# stm32_bob.net
KiCad netlist of a schematic drawn in EAGLE
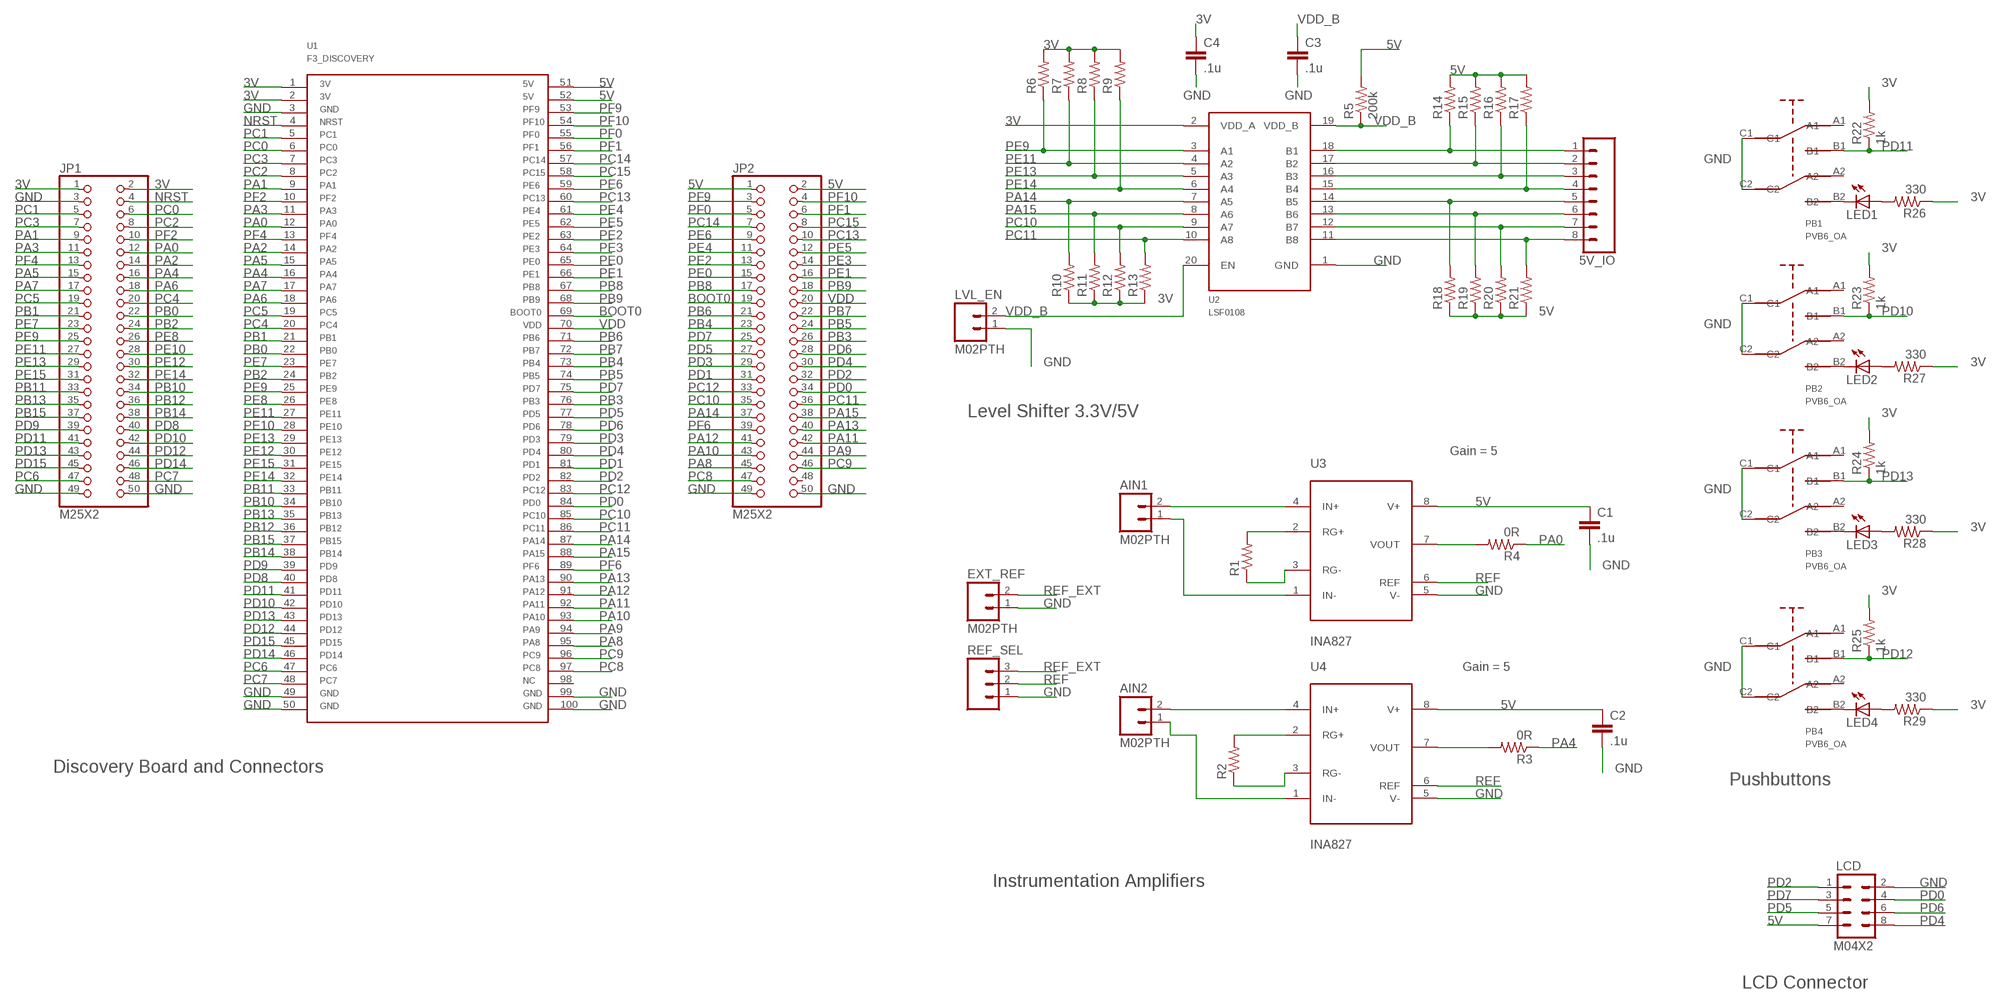
[diagram p0: schematic, sheet 1]

(export (version "E")
  (design (tool "Eeschema 10.0.6"))
  (components
    (comp (ref "5V_IO")
      (value "M081X08")
      (footprint "eagle-import:1X08")
      (libsource (lib "eagle-import") (part "M081X08"))
    )
    (comp (ref "AIN1")
      (value "M02PTH")
      (footprint "eagle-import:1X02")
      (libsource (lib "eagle-import") (part "M02PTH"))
    )
    (comp (ref "AIN2")
      (value "M02PTH")
      (footprint "eagle-import:1X02")
      (libsource (lib "eagle-import") (part "M02PTH"))
    )
    (comp (ref "C1")
      (value ".1u")
      (footprint "eagle-import:C0805")
      (libsource (lib "eagle-import") (part "C-EUC0805"))
    )
    (comp (ref "C2")
      (value ".1u")
      (footprint "eagle-import:C0805")
      (libsource (lib "eagle-import") (part "C-EUC0805"))
    )
    (comp (ref "C3")
      (value ".1u")
      (footprint "eagle-import:C0805")
      (libsource (lib "eagle-import") (part "C-EUC0805"))
    )
    (comp (ref "C4")
      (value ".1u")
      (footprint "eagle-import:C0805")
      (libsource (lib "eagle-import") (part "C-EUC0805"))
    )
    (comp (ref "EXT_REF")
      (value "M02PTH")
      (footprint "eagle-import:1X02")
      (libsource (lib "eagle-import") (part "M02PTH"))
    )
    (comp (ref "JP1")
      (value "M25X2")
      (footprint "eagle-import:2X25")
      (libsource (lib "eagle-import") (part "M25X2"))
    )
    (comp (ref "JP2")
      (value "M25X2")
      (footprint "eagle-import:2X25")
      (libsource (lib "eagle-import") (part "M25X2"))
    )
    (comp (ref "LCD")
      (value "M04X2")
      (footprint "eagle-import:2X4")
      (libsource (lib "eagle-import") (part "M04X2"))
    )
    (comp (ref "LED1")
      (value "LED1206")
      (footprint "eagle-import:LED-1206")
      (libsource (lib "eagle-import") (part "LED1206"))
    )
    (comp (ref "LED2")
      (value "LED1206")
      (footprint "eagle-import:LED-1206")
      (libsource (lib "eagle-import") (part "LED1206"))
    )
    (comp (ref "LED3")
      (value "LED1206")
      (footprint "eagle-import:LED-1206")
      (libsource (lib "eagle-import") (part "LED1206"))
    )
    (comp (ref "LED4")
      (value "LED1206")
      (footprint "eagle-import:LED-1206")
      (libsource (lib "eagle-import") (part "LED1206"))
    )
    (comp (ref "LVL_EN")
      (value "M02PTH")
      (footprint "eagle-import:1X02")
      (libsource (lib "eagle-import") (part "M02PTH"))
    )
    (comp (ref "PB1")
      (value "PVB6_OA")
      (footprint "eagle-import:PVB6_OA")
      (libsource (lib "eagle-import") (part "PVB6_OA"))
    )
    (comp (ref "PB2")
      (value "PVB6_OA")
      (footprint "eagle-import:PVB6_OA")
      (libsource (lib "eagle-import") (part "PVB6_OA"))
    )
    (comp (ref "PB3")
      (value "PVB6_OA")
      (footprint "eagle-import:PVB6_OA")
      (libsource (lib "eagle-import") (part "PVB6_OA"))
    )
    (comp (ref "PB4")
      (value "PVB6_OA")
      (footprint "eagle-import:PVB6_OA")
      (libsource (lib "eagle-import") (part "PVB6_OA"))
    )
    (comp (ref "R1")
      (value "R-US_R1206")
      (footprint "eagle-import:R1206")
      (libsource (lib "eagle-import") (part "R-US_R1206"))
    )
    (comp (ref "R2")
      (value "R-US_R1206")
      (footprint "eagle-import:R1206")
      (libsource (lib "eagle-import") (part "R-US_R1206"))
    )
    (comp (ref "R3")
      (value "0R")
      (footprint "eagle-import:R1206")
      (libsource (lib "eagle-import") (part "R-US_R1206"))
    )
    (comp (ref "R4")
      (value "0R")
      (footprint "eagle-import:R1206")
      (libsource (lib "eagle-import") (part "R-US_R1206"))
    )
    (comp (ref "R5")
      (value "200k")
      (footprint "eagle-import:R0805")
      (libsource (lib "eagle-import") (part "R-US_R0805"))
    )
    (comp (ref "R6")
      (value "R-US_R0805")
      (footprint "eagle-import:R0805")
      (libsource (lib "eagle-import") (part "R-US_R0805"))
    )
    (comp (ref "R7")
      (value "R-US_R0805")
      (footprint "eagle-import:R0805")
      (libsource (lib "eagle-import") (part "R-US_R0805"))
    )
    (comp (ref "R8")
      (value "R-US_R0805")
      (footprint "eagle-import:R0805")
      (libsource (lib "eagle-import") (part "R-US_R0805"))
    )
    (comp (ref "R9")
      (value "R-US_R0805")
      (footprint "eagle-import:R0805")
      (libsource (lib "eagle-import") (part "R-US_R0805"))
    )
    (comp (ref "R10")
      (value "R-US_R0805")
      (footprint "eagle-import:R0805")
      (libsource (lib "eagle-import") (part "R-US_R0805"))
    )
    (comp (ref "R11")
      (value "R-US_R0805")
      (footprint "eagle-import:R0805")
      (libsource (lib "eagle-import") (part "R-US_R0805"))
    )
    (comp (ref "R12")
      (value "R-US_R0805")
      (footprint "eagle-import:R0805")
      (libsource (lib "eagle-import") (part "R-US_R0805"))
    )
    (comp (ref "R13")
      (value "R-US_R0805")
      (footprint "eagle-import:R0805")
      (libsource (lib "eagle-import") (part "R-US_R0805"))
    )
    (comp (ref "R14")
      (value "R-US_R0805")
      (footprint "eagle-import:R0805")
      (libsource (lib "eagle-import") (part "R-US_R0805"))
    )
    (comp (ref "R15")
      (value "R-US_R0805")
      (footprint "eagle-import:R0805")
      (libsource (lib "eagle-import") (part "R-US_R0805"))
    )
    (comp (ref "R16")
      (value "R-US_R0805")
      (footprint "eagle-import:R0805")
      (libsource (lib "eagle-import") (part "R-US_R0805"))
    )
    (comp (ref "R17")
      (value "R-US_R0805")
      (footprint "eagle-import:R0805")
      (libsource (lib "eagle-import") (part "R-US_R0805"))
    )
    (comp (ref "R18")
      (value "R-US_R0805")
      (footprint "eagle-import:R0805")
      (libsource (lib "eagle-import") (part "R-US_R0805"))
    )
    (comp (ref "R19")
      (value "R-US_R0805")
      (footprint "eagle-import:R0805")
      (libsource (lib "eagle-import") (part "R-US_R0805"))
    )
    (comp (ref "R20")
      (value "R-US_R0805")
      (footprint "eagle-import:R0805")
      (libsource (lib "eagle-import") (part "R-US_R0805"))
    )
    (comp (ref "R21")
      (value "R-US_R0805")
      (footprint "eagle-import:R0805")
      (libsource (lib "eagle-import") (part "R-US_R0805"))
    )
    (comp (ref "R22")
      (value "1k")
      (footprint "eagle-import:R0805")
      (libsource (lib "eagle-import") (part "R-US_R0805"))
    )
    (comp (ref "R23")
      (value "1k")
      (footprint "eagle-import:R0805")
      (libsource (lib "eagle-import") (part "R-US_R0805"))
    )
    (comp (ref "R24")
      (value "1k")
      (footprint "eagle-import:R0805")
      (libsource (lib "eagle-import") (part "R-US_R0805"))
    )
    (comp (ref "R25")
      (value "1k")
      (footprint "eagle-import:R0805")
      (libsource (lib "eagle-import") (part "R-US_R0805"))
    )
    (comp (ref "R26")
      (value "330")
      (footprint "eagle-import:R0805")
      (libsource (lib "eagle-import") (part "R-US_R0805"))
    )
    (comp (ref "R27")
      (value "330")
      (footprint "eagle-import:R0805")
      (libsource (lib "eagle-import") (part "R-US_R0805"))
    )
    (comp (ref "R28")
      (value "330")
      (footprint "eagle-import:R0805")
      (libsource (lib "eagle-import") (part "R-US_R0805"))
    )
    (comp (ref "R29")
      (value "330")
      (footprint "eagle-import:R0805")
      (libsource (lib "eagle-import") (part "R-US_R0805"))
    )
    (comp (ref "REF_SEL")
      (value "M03PTH")
      (footprint "eagle-import:1X03")
      (libsource (lib "eagle-import") (part "M03PTH"))
    )
    (comp (ref "U1")
      (value "F3_DISCOVERY")
      (footprint "eagle-import:F3_DISCOVERY")
      (libsource (lib "eagle-import") (part "F3_DISCOVERY"))
    )
    (comp (ref "U2")
      (value "LSF0108")
      (footprint "eagle-import:LSF0108")
      (libsource (lib "eagle-import") (part "LSF0108"))
    )
    (comp (ref "U3")
      (value "INA827")
      (footprint "eagle-import:MSOP8")
      (libsource (lib "eagle-import") (part "INA827"))
    )
    (comp (ref "U4")
      (value "INA827")
      (footprint "eagle-import:MSOP8")
      (libsource (lib "eagle-import") (part "INA827"))
    )
  )
  (nets
    (net (code "1") (name "/3V") (class "Default")
      (node (ref "C4") (pin "1") (pinfunction "1_1") (pintype "passive"))
      (node (ref "JP1") (pin "1") (pinfunction "1_1") (pintype "passive"))
      (node (ref "JP1") (pin "2") (pinfunction "2_2") (pintype "passive"))
      (node (ref "R10") (pin "1") (pinfunction "1_1") (pintype "passive"))
      (node (ref "R11") (pin "1") (pinfunction "1_1") (pintype "passive"))
      (node (ref "R12") (pin "1") (pinfunction "1_1") (pintype "passive"))
      (node (ref "R13") (pin "1") (pinfunction "1_1") (pintype "passive"))
      (node (ref "R22") (pin "2") (pinfunction "2_2") (pintype "passive"))
      (node (ref "R23") (pin "2") (pinfunction "2_2") (pintype "passive"))
      (node (ref "R24") (pin "2") (pinfunction "2_2") (pintype "passive"))
      (node (ref "R25") (pin "2") (pinfunction "2_2") (pintype "passive"))
      (node (ref "R26") (pin "1") (pinfunction "1_1") (pintype "passive"))
      (node (ref "R27") (pin "1") (pinfunction "1_1") (pintype "passive"))
      (node (ref "R28") (pin "1") (pinfunction "1_1") (pintype "passive"))
      (node (ref "R29") (pin "1") (pinfunction "1_1") (pintype "passive"))
      (node (ref "R6") (pin "2") (pinfunction "2_2") (pintype "passive"))
      (node (ref "R7") (pin "2") (pinfunction "2_2") (pintype "passive"))
      (node (ref "R8") (pin "2") (pinfunction "2_2") (pintype "passive"))
      (node (ref "R9") (pin "2") (pinfunction "2_2") (pintype "passive"))
      (node (ref "U1") (pin "1") (pinfunction "P$1_1") (pintype "bidirectional"))
      (node (ref "U1") (pin "2") (pinfunction "P$2_2") (pintype "bidirectional"))
      (node (ref "U2") (pin "2") (pinfunction "VDD_A_2") (pintype "bidirectional"))
    )
    (net (code "2") (name "/5V") (class "Default")
      (node (ref "C1") (pin "1") (pinfunction "1_1") (pintype "passive"))
      (node (ref "C2") (pin "1") (pinfunction "1_1") (pintype "passive"))
      (node (ref "JP2") (pin "1") (pinfunction "1_1") (pintype "passive"))
      (node (ref "JP2") (pin "2") (pinfunction "2_2") (pintype "passive"))
      (node (ref "LCD") (pin "7") (pinfunction "7_7") (pintype "passive"))
      (node (ref "R14") (pin "2") (pinfunction "2_2") (pintype "passive"))
      (node (ref "R15") (pin "2") (pinfunction "2_2") (pintype "passive"))
      (node (ref "R16") (pin "2") (pinfunction "2_2") (pintype "passive"))
      (node (ref "R17") (pin "2") (pinfunction "2_2") (pintype "passive"))
      (node (ref "R18") (pin "1") (pinfunction "1_1") (pintype "passive"))
      (node (ref "R19") (pin "1") (pinfunction "1_1") (pintype "passive"))
      (node (ref "R20") (pin "1") (pinfunction "1_1") (pintype "passive"))
      (node (ref "R21") (pin "1") (pinfunction "1_1") (pintype "passive"))
      (node (ref "R5") (pin "2") (pinfunction "2_2") (pintype "passive"))
      (node (ref "U1") (pin "51") (pinfunction "P$51_51") (pintype "bidirectional"))
      (node (ref "U1") (pin "52") (pinfunction "P$52_52") (pintype "bidirectional"))
      (node (ref "U3") (pin "8") (pinfunction "V+_8") (pintype "bidirectional"))
      (node (ref "U4") (pin "8") (pinfunction "V+_8") (pintype "bidirectional"))
    )
    (net (code "3") (name "/BOOT0") (class "Default")
      (node (ref "JP2") (pin "19") (pinfunction "19_19") (pintype "passive"))
      (node (ref "U1") (pin "69") (pinfunction "P$69_69") (pintype "bidirectional"))
    )
    (net (code "4") (name "/GND") (class "Default")
      (node (ref "C1") (pin "2") (pinfunction "2_2") (pintype "passive"))
      (node (ref "C2") (pin "2") (pinfunction "2_2") (pintype "passive"))
      (node (ref "C3") (pin "2") (pinfunction "2_2") (pintype "passive"))
      (node (ref "C4") (pin "2") (pinfunction "2_2") (pintype "passive"))
      (node (ref "EXT_REF") (pin "1") (pinfunction "1_1") (pintype "passive"))
      (node (ref "JP1") (pin "3") (pinfunction "3_3") (pintype "passive"))
      (node (ref "JP1") (pin "49") (pinfunction "49_49") (pintype "passive"))
      (node (ref "JP1") (pin "50") (pinfunction "50_50") (pintype "passive"))
      (node (ref "JP2") (pin "49") (pinfunction "49_49") (pintype "passive"))
      (node (ref "JP2") (pin "50") (pinfunction "50_50") (pintype "passive"))
      (node (ref "LCD") (pin "2") (pinfunction "2_2") (pintype "passive"))
      (node (ref "LVL_EN") (pin "1") (pinfunction "1_1") (pintype "passive"))
      (node (ref "PB1") (pin "C1") (pinfunction "C1_C1") (pintype "bidirectional"))
      (node (ref "PB1") (pin "C2") (pinfunction "C2_C2") (pintype "bidirectional"))
      (node (ref "PB2") (pin "C1") (pinfunction "C1_C1") (pintype "bidirectional"))
      (node (ref "PB2") (pin "C2") (pinfunction "C2_C2") (pintype "bidirectional"))
      (node (ref "PB3") (pin "C1") (pinfunction "C1_C1") (pintype "bidirectional"))
      (node (ref "PB3") (pin "C2") (pinfunction "C2_C2") (pintype "bidirectional"))
      (node (ref "PB4") (pin "C1") (pinfunction "C1_C1") (pintype "bidirectional"))
      (node (ref "PB4") (pin "C2") (pinfunction "C2_C2") (pintype "bidirectional"))
      (node (ref "REF_SEL") (pin "1") (pinfunction "1_1") (pintype "passive"))
      (node (ref "U1") (pin "100") (pinfunction "P$100_100") (pintype "bidirectional"))
      (node (ref "U1") (pin "3") (pinfunction "P$3_3") (pintype "bidirectional"))
      (node (ref "U1") (pin "49") (pinfunction "P$49_49") (pintype "bidirectional"))
      (node (ref "U1") (pin "50") (pinfunction "P$50_50") (pintype "bidirectional"))
      (node (ref "U1") (pin "99") (pinfunction "P$99_99") (pintype "bidirectional"))
      (node (ref "U2") (pin "1") (pinfunction "GND_1") (pintype "bidirectional"))
      (node (ref "U3") (pin "5") (pinfunction "V-_5") (pintype "bidirectional"))
      (node (ref "U4") (pin "5") (pinfunction "V-_5") (pintype "bidirectional"))
    )
    (net (code "5") (name "/NRST") (class "Default")
      (node (ref "JP1") (pin "4") (pinfunction "4_4") (pintype "passive"))
      (node (ref "U1") (pin "4") (pinfunction "P$4_4") (pintype "bidirectional"))
    )
    (net (code "6") (name "/PA0") (class "Default")
      (node (ref "JP1") (pin "12") (pinfunction "12_12") (pintype "passive"))
      (node (ref "R4") (pin "1") (pinfunction "1_1") (pintype "passive"))
      (node (ref "U1") (pin "12") (pinfunction "P$12_12") (pintype "bidirectional"))
    )
    (net (code "7") (name "/PA1") (class "Default")
      (node (ref "JP1") (pin "9") (pinfunction "9_9") (pintype "passive"))
      (node (ref "U1") (pin "9") (pinfunction "P$9_9") (pintype "bidirectional"))
    )
    (net (code "8") (name "/PA2") (class "Default")
      (node (ref "JP1") (pin "14") (pinfunction "14_14") (pintype "passive"))
      (node (ref "U1") (pin "14") (pinfunction "P$14_14") (pintype "bidirectional"))
    )
    (net (code "9") (name "/PA3") (class "Default")
      (node (ref "JP1") (pin "11") (pinfunction "11_11") (pintype "passive"))
      (node (ref "U1") (pin "11") (pinfunction "P$11_11") (pintype "bidirectional"))
    )
    (net (code "10") (name "/PA4") (class "Default")
      (node (ref "JP1") (pin "16") (pinfunction "16_16") (pintype "passive"))
      (node (ref "R3") (pin "1") (pinfunction "1_1") (pintype "passive"))
      (node (ref "U1") (pin "16") (pinfunction "P$16_16") (pintype "bidirectional"))
    )
    (net (code "11") (name "/PA5") (class "Default")
      (node (ref "JP1") (pin "15") (pinfunction "15_15") (pintype "passive"))
      (node (ref "U1") (pin "15") (pinfunction "P$15_15") (pintype "bidirectional"))
    )
    (net (code "12") (name "/PA6") (class "Default")
      (node (ref "JP1") (pin "18") (pinfunction "18_18") (pintype "passive"))
      (node (ref "U1") (pin "18") (pinfunction "P$18_18") (pintype "bidirectional"))
    )
    (net (code "13") (name "/PA7") (class "Default")
      (node (ref "JP1") (pin "17") (pinfunction "17_17") (pintype "passive"))
      (node (ref "U1") (pin "17") (pinfunction "P$17_17") (pintype "bidirectional"))
    )
    (net (code "14") (name "/PA8") (class "Default")
      (node (ref "JP2") (pin "45") (pinfunction "45_45") (pintype "passive"))
      (node (ref "U1") (pin "95") (pinfunction "P$95_95") (pintype "bidirectional"))
    )
    (net (code "15") (name "/PA9") (class "Default")
      (node (ref "JP2") (pin "44") (pinfunction "44_44") (pintype "passive"))
      (node (ref "U1") (pin "94") (pinfunction "P$94_94") (pintype "bidirectional"))
    )
    (net (code "16") (name "/PA10") (class "Default")
      (node (ref "JP2") (pin "43") (pinfunction "43_43") (pintype "passive"))
      (node (ref "U1") (pin "93") (pinfunction "P$93_93") (pintype "bidirectional"))
    )
    (net (code "17") (name "/PA11") (class "Default")
      (node (ref "JP2") (pin "42") (pinfunction "42_42") (pintype "passive"))
      (node (ref "U1") (pin "92") (pinfunction "P$92_92") (pintype "bidirectional"))
    )
    (net (code "18") (name "/PA12") (class "Default")
      (node (ref "JP2") (pin "41") (pinfunction "41_41") (pintype "passive"))
      (node (ref "U1") (pin "91") (pinfunction "P$91_91") (pintype "bidirectional"))
    )
    (net (code "19") (name "/PA13") (class "Default")
      (node (ref "JP2") (pin "40") (pinfunction "40_40") (pintype "passive"))
      (node (ref "U1") (pin "90") (pinfunction "P$90_90") (pintype "bidirectional"))
    )
    (net (code "20") (name "/PA14") (class "Default")
      (node (ref "JP2") (pin "37") (pinfunction "37_37") (pintype "passive"))
      (node (ref "R10") (pin "2") (pinfunction "2_2") (pintype "passive"))
      (node (ref "U1") (pin "87") (pinfunction "P$87_87") (pintype "bidirectional"))
      (node (ref "U2") (pin "7") (pinfunction "A5_7") (pintype "bidirectional"))
    )
    (net (code "21") (name "/PA15") (class "Default")
      (node (ref "JP2") (pin "38") (pinfunction "38_38") (pintype "passive"))
      (node (ref "R11") (pin "2") (pinfunction "2_2") (pintype "passive"))
      (node (ref "U1") (pin "88") (pinfunction "P$88_88") (pintype "bidirectional"))
      (node (ref "U2") (pin "8") (pinfunction "A6_8") (pintype "bidirectional"))
    )
    (net (code "22") (name "/PB0") (class "Default")
      (node (ref "JP1") (pin "22") (pinfunction "22_22") (pintype "passive"))
      (node (ref "U1") (pin "22") (pinfunction "P$22_22") (pintype "bidirectional"))
    )
    (net (code "23") (name "/PB1") (class "Default")
      (node (ref "JP1") (pin "21") (pinfunction "21_21") (pintype "passive"))
      (node (ref "U1") (pin "21") (pinfunction "P$21_21") (pintype "bidirectional"))
    )
    (net (code "24") (name "/PB2") (class "Default")
      (node (ref "JP1") (pin "24") (pinfunction "24_24") (pintype "passive"))
      (node (ref "U1") (pin "24") (pinfunction "P$24_24") (pintype "bidirectional"))
    )
    (net (code "25") (name "/PB3") (class "Default")
      (node (ref "JP2") (pin "26") (pinfunction "26_26") (pintype "passive"))
      (node (ref "U1") (pin "76") (pinfunction "P$76_76") (pintype "bidirectional"))
    )
    (net (code "26") (name "/PB4") (class "Default")
      (node (ref "JP2") (pin "23") (pinfunction "23_23") (pintype "passive"))
      (node (ref "U1") (pin "73") (pinfunction "P$73_73") (pintype "bidirectional"))
    )
    (net (code "27") (name "/PB5") (class "Default")
      (node (ref "JP2") (pin "24") (pinfunction "24_24") (pintype "passive"))
      (node (ref "U1") (pin "74") (pinfunction "P$74_74") (pintype "bidirectional"))
    )
    (net (code "28") (name "/PB6") (class "Default")
      (node (ref "JP2") (pin "21") (pinfunction "21_21") (pintype "passive"))
      (node (ref "U1") (pin "71") (pinfunction "P$71_71") (pintype "bidirectional"))
    )
    (net (code "29") (name "/PB7") (class "Default")
      (node (ref "JP2") (pin "22") (pinfunction "22_22") (pintype "passive"))
      (node (ref "U1") (pin "72") (pinfunction "P$72_72") (pintype "bidirectional"))
    )
    (net (code "30") (name "/PB8") (class "Default")
      (node (ref "JP2") (pin "17") (pinfunction "17_17") (pintype "passive"))
      (node (ref "U1") (pin "67") (pinfunction "P$67_67") (pintype "bidirectional"))
    )
    (net (code "31") (name "/PB9") (class "Default")
      (node (ref "JP2") (pin "18") (pinfunction "18_18") (pintype "passive"))
      (node (ref "U1") (pin "68") (pinfunction "P$68_68") (pintype "bidirectional"))
    )
    (net (code "32") (name "/PB10") (class "Default")
      (node (ref "JP1") (pin "34") (pinfunction "34_34") (pintype "passive"))
      (node (ref "U1") (pin "34") (pinfunction "P$34_34") (pintype "bidirectional"))
    )
    (net (code "33") (name "/PB11") (class "Default")
      (node (ref "JP1") (pin "33") (pinfunction "33_33") (pintype "passive"))
      (node (ref "U1") (pin "33") (pinfunction "P$33_33") (pintype "bidirectional"))
    )
    (net (code "34") (name "/PB12") (class "Default")
      (node (ref "JP1") (pin "36") (pinfunction "36_36") (pintype "passive"))
      (node (ref "U1") (pin "36") (pinfunction "P$36_36") (pintype "bidirectional"))
    )
    (net (code "35") (name "/PB13") (class "Default")
      (node (ref "JP1") (pin "35") (pinfunction "35_35") (pintype "passive"))
      (node (ref "U1") (pin "35") (pinfunction "P$35_35") (pintype "bidirectional"))
    )
    (net (code "36") (name "/PB14") (class "Default")
      (node (ref "JP1") (pin "38") (pinfunction "38_38") (pintype "passive"))
      (node (ref "U1") (pin "38") (pinfunction "P$38_38") (pintype "bidirectional"))
    )
    (net (code "37") (name "/PB15") (class "Default")
      (node (ref "JP1") (pin "37") (pinfunction "37_37") (pintype "passive"))
      (node (ref "U1") (pin "37") (pinfunction "P$37_37") (pintype "bidirectional"))
    )
    (net (code "38") (name "/PC0") (class "Default")
      (node (ref "JP1") (pin "6") (pinfunction "6_6") (pintype "passive"))
      (node (ref "U1") (pin "6") (pinfunction "P$6_6") (pintype "bidirectional"))
    )
    (net (code "39") (name "/PC1") (class "Default")
      (node (ref "JP1") (pin "5") (pinfunction "5_5") (pintype "passive"))
      (node (ref "U1") (pin "5") (pinfunction "P$5_5") (pintype "bidirectional"))
    )
    (net (code "40") (name "/PC2") (class "Default")
      (node (ref "JP1") (pin "8") (pinfunction "8_8") (pintype "passive"))
      (node (ref "U1") (pin "8") (pinfunction "P$8_8") (pintype "bidirectional"))
    )
    (net (code "41") (name "/PC3") (class "Default")
      (node (ref "JP1") (pin "7") (pinfunction "7_7") (pintype "passive"))
      (node (ref "U1") (pin "7") (pinfunction "P$7_7") (pintype "bidirectional"))
    )
    (net (code "42") (name "/PC4") (class "Default")
      (node (ref "JP1") (pin "20") (pinfunction "20_20") (pintype "passive"))
      (node (ref "U1") (pin "20") (pinfunction "P$20_20") (pintype "bidirectional"))
    )
    (net (code "43") (name "/PC5") (class "Default")
      (node (ref "JP1") (pin "19") (pinfunction "19_19") (pintype "passive"))
      (node (ref "U1") (pin "19") (pinfunction "P$19_19") (pintype "bidirectional"))
    )
    (net (code "44") (name "/PC6") (class "Default")
      (node (ref "JP1") (pin "47") (pinfunction "47_47") (pintype "passive"))
      (node (ref "U1") (pin "47") (pinfunction "P$47_47") (pintype "bidirectional"))
    )
    (net (code "45") (name "/PC7") (class "Default")
      (node (ref "JP1") (pin "48") (pinfunction "48_48") (pintype "passive"))
      (node (ref "U1") (pin "48") (pinfunction "P$48_48") (pintype "bidirectional"))
    )
    (net (code "46") (name "/PC8") (class "Default")
      (node (ref "JP2") (pin "47") (pinfunction "47_47") (pintype "passive"))
      (node (ref "U1") (pin "97") (pinfunction "P$97_97") (pintype "bidirectional"))
    )
    (net (code "47") (name "/PC9") (class "Default")
      (node (ref "JP2") (pin "46") (pinfunction "46_46") (pintype "passive"))
      (node (ref "U1") (pin "96") (pinfunction "P$96_96") (pintype "bidirectional"))
    )
    (net (code "48") (name "/PC10") (class "Default")
      (node (ref "JP2") (pin "35") (pinfunction "35_35") (pintype "passive"))
      (node (ref "R12") (pin "2") (pinfunction "2_2") (pintype "passive"))
      (node (ref "U1") (pin "85") (pinfunction "P$85_85") (pintype "bidirectional"))
      (node (ref "U2") (pin "9") (pinfunction "A7_9") (pintype "bidirectional"))
    )
    (net (code "49") (name "/PC11") (class "Default")
      (node (ref "JP2") (pin "36") (pinfunction "36_36") (pintype "passive"))
      (node (ref "R13") (pin "2") (pinfunction "2_2") (pintype "passive"))
      (node (ref "U1") (pin "86") (pinfunction "P$86_86") (pintype "bidirectional"))
      (node (ref "U2") (pin "10") (pinfunction "A8_10") (pintype "bidirectional"))
    )
    (net (code "50") (name "/PC12") (class "Default")
      (node (ref "JP2") (pin "33") (pinfunction "33_33") (pintype "passive"))
      (node (ref "U1") (pin "83") (pinfunction "P$83_83") (pintype "bidirectional"))
    )
    (net (code "51") (name "/PC13") (class "Default")
      (node (ref "JP2") (pin "10") (pinfunction "10_10") (pintype "passive"))
      (node (ref "U1") (pin "60") (pinfunction "P$60_60") (pintype "bidirectional"))
    )
    (net (code "52") (name "/PC14") (class "Default")
      (node (ref "JP2") (pin "7") (pinfunction "7_7") (pintype "passive"))
      (node (ref "U1") (pin "57") (pinfunction "P$57_57") (pintype "bidirectional"))
    )
    (net (code "53") (name "/PC15") (class "Default")
      (node (ref "JP2") (pin "8") (pinfunction "8_8") (pintype "passive"))
      (node (ref "U1") (pin "58") (pinfunction "P$58_58") (pintype "bidirectional"))
    )
    (net (code "54") (name "/PD0") (class "Default")
      (node (ref "JP2") (pin "34") (pinfunction "34_34") (pintype "passive"))
      (node (ref "LCD") (pin "4") (pinfunction "4_4") (pintype "passive"))
      (node (ref "U1") (pin "84") (pinfunction "P$84_84") (pintype "bidirectional"))
    )
    (net (code "55") (name "/PD1") (class "Default")
      (node (ref "JP2") (pin "31") (pinfunction "31_31") (pintype "passive"))
      (node (ref "U1") (pin "81") (pinfunction "P$81_81") (pintype "bidirectional"))
    )
    (net (code "56") (name "/PD2") (class "Default")
      (node (ref "JP2") (pin "32") (pinfunction "32_32") (pintype "passive"))
      (node (ref "LCD") (pin "1") (pinfunction "1_1") (pintype "passive"))
      (node (ref "U1") (pin "82") (pinfunction "P$82_82") (pintype "bidirectional"))
    )
    (net (code "57") (name "/PD3") (class "Default")
      (node (ref "JP2") (pin "29") (pinfunction "29_29") (pintype "passive"))
      (node (ref "U1") (pin "79") (pinfunction "P$79_79") (pintype "bidirectional"))
    )
    (net (code "58") (name "/PD4") (class "Default")
      (node (ref "JP2") (pin "30") (pinfunction "30_30") (pintype "passive"))
      (node (ref "LCD") (pin "8") (pinfunction "8_8") (pintype "passive"))
      (node (ref "U1") (pin "80") (pinfunction "P$80_80") (pintype "bidirectional"))
    )
    (net (code "59") (name "/PD5") (class "Default")
      (node (ref "JP2") (pin "27") (pinfunction "27_27") (pintype "passive"))
      (node (ref "LCD") (pin "5") (pinfunction "5_5") (pintype "passive"))
      (node (ref "U1") (pin "77") (pinfunction "P$77_77") (pintype "bidirectional"))
    )
    (net (code "60") (name "/PD6") (class "Default")
      (node (ref "JP2") (pin "28") (pinfunction "28_28") (pintype "passive"))
      (node (ref "LCD") (pin "6") (pinfunction "6_6") (pintype "passive"))
      (node (ref "U1") (pin "78") (pinfunction "P$78_78") (pintype "bidirectional"))
    )
    (net (code "61") (name "/PD7") (class "Default")
      (node (ref "JP2") (pin "25") (pinfunction "25_25") (pintype "passive"))
      (node (ref "LCD") (pin "3") (pinfunction "3_3") (pintype "passive"))
      (node (ref "U1") (pin "75") (pinfunction "P$75_75") (pintype "bidirectional"))
    )
    (net (code "62") (name "/PD8") (class "Default")
      (node (ref "JP1") (pin "40") (pinfunction "40_40") (pintype "passive"))
      (node (ref "U1") (pin "40") (pinfunction "P$40_40") (pintype "bidirectional"))
    )
    (net (code "63") (name "/PD9") (class "Default")
      (node (ref "JP1") (pin "39") (pinfunction "39_39") (pintype "passive"))
      (node (ref "U1") (pin "39") (pinfunction "P$39_39") (pintype "bidirectional"))
    )
    (net (code "64") (name "/PD10") (class "Default")
      (node (ref "JP1") (pin "42") (pinfunction "42_42") (pintype "passive"))
      (node (ref "PB2") (pin "B1") (pinfunction "B1_B1") (pintype "bidirectional"))
      (node (ref "R23") (pin "1") (pinfunction "1_1") (pintype "passive"))
      (node (ref "U1") (pin "42") (pinfunction "P$42_42") (pintype "bidirectional"))
    )
    (net (code "65") (name "/PD11") (class "Default")
      (node (ref "JP1") (pin "41") (pinfunction "41_41") (pintype "passive"))
      (node (ref "PB1") (pin "B1") (pinfunction "B1_B1") (pintype "bidirectional"))
      (node (ref "R22") (pin "1") (pinfunction "1_1") (pintype "passive"))
      (node (ref "U1") (pin "41") (pinfunction "P$41_41") (pintype "bidirectional"))
    )
    (net (code "66") (name "/PD12") (class "Default")
      (node (ref "JP1") (pin "44") (pinfunction "44_44") (pintype "passive"))
      (node (ref "PB4") (pin "B1") (pinfunction "B1_B1") (pintype "bidirectional"))
      (node (ref "R25") (pin "1") (pinfunction "1_1") (pintype "passive"))
      (node (ref "U1") (pin "44") (pinfunction "P$44_44") (pintype "bidirectional"))
    )
    (net (code "67") (name "/PD13") (class "Default")
      (node (ref "JP1") (pin "43") (pinfunction "43_43") (pintype "passive"))
      (node (ref "PB3") (pin "B1") (pinfunction "B1_B1") (pintype "bidirectional"))
      (node (ref "R24") (pin "1") (pinfunction "1_1") (pintype "passive"))
      (node (ref "U1") (pin "43") (pinfunction "P$43_43") (pintype "bidirectional"))
    )
    (net (code "68") (name "/PD14") (class "Default")
      (node (ref "JP1") (pin "46") (pinfunction "46_46") (pintype "passive"))
      (node (ref "U1") (pin "46") (pinfunction "P$46_46") (pintype "bidirectional"))
    )
    (net (code "69") (name "/PD15") (class "Default")
      (node (ref "JP1") (pin "45") (pinfunction "45_45") (pintype "passive"))
      (node (ref "U1") (pin "45") (pinfunction "P$45_45") (pintype "bidirectional"))
    )
    (net (code "70") (name "/PE0") (class "Default")
      (node (ref "JP2") (pin "15") (pinfunction "15_15") (pintype "passive"))
      (node (ref "U1") (pin "65") (pinfunction "P$65_65") (pintype "bidirectional"))
    )
    (net (code "71") (name "/PE1") (class "Default")
      (node (ref "JP2") (pin "16") (pinfunction "16_16") (pintype "passive"))
      (node (ref "U1") (pin "66") (pinfunction "P$66_66") (pintype "bidirectional"))
    )
    (net (code "72") (name "/PE2") (class "Default")
      (node (ref "JP2") (pin "13") (pinfunction "13_13") (pintype "passive"))
      (node (ref "U1") (pin "63") (pinfunction "P$63_63") (pintype "bidirectional"))
    )
    (net (code "73") (name "/PE3") (class "Default")
      (node (ref "JP2") (pin "14") (pinfunction "14_14") (pintype "passive"))
      (node (ref "U1") (pin "64") (pinfunction "P$64_64") (pintype "bidirectional"))
    )
    (net (code "74") (name "/PE4") (class "Default")
      (node (ref "JP2") (pin "11") (pinfunction "11_11") (pintype "passive"))
      (node (ref "U1") (pin "61") (pinfunction "P$61_61") (pintype "bidirectional"))
    )
    (net (code "75") (name "/PE5") (class "Default")
      (node (ref "JP2") (pin "12") (pinfunction "12_12") (pintype "passive"))
      (node (ref "U1") (pin "62") (pinfunction "P$62_62") (pintype "bidirectional"))
    )
    (net (code "76") (name "/PE6") (class "Default")
      (node (ref "JP2") (pin "9") (pinfunction "9_9") (pintype "passive"))
      (node (ref "U1") (pin "59") (pinfunction "P$59_59") (pintype "bidirectional"))
    )
    (net (code "77") (name "/PE7") (class "Default")
      (node (ref "JP1") (pin "23") (pinfunction "23_23") (pintype "passive"))
      (node (ref "U1") (pin "23") (pinfunction "P$23_23") (pintype "bidirectional"))
    )
    (net (code "78") (name "/PE8") (class "Default")
      (node (ref "JP1") (pin "26") (pinfunction "26_26") (pintype "passive"))
      (node (ref "U1") (pin "26") (pinfunction "P$26_26") (pintype "bidirectional"))
    )
    (net (code "79") (name "/PE9") (class "Default")
      (node (ref "JP1") (pin "25") (pinfunction "25_25") (pintype "passive"))
      (node (ref "R6") (pin "1") (pinfunction "1_1") (pintype "passive"))
      (node (ref "U1") (pin "25") (pinfunction "P$25_25") (pintype "bidirectional"))
      (node (ref "U2") (pin "3") (pinfunction "A1_3") (pintype "bidirectional"))
    )
    (net (code "80") (name "/PE10") (class "Default")
      (node (ref "JP1") (pin "28") (pinfunction "28_28") (pintype "passive"))
      (node (ref "U1") (pin "28") (pinfunction "P$28_28") (pintype "bidirectional"))
    )
    (net (code "81") (name "/PE11") (class "Default")
      (node (ref "JP1") (pin "27") (pinfunction "27_27") (pintype "passive"))
      (node (ref "R7") (pin "1") (pinfunction "1_1") (pintype "passive"))
      (node (ref "U1") (pin "27") (pinfunction "P$27_27") (pintype "bidirectional"))
      (node (ref "U2") (pin "4") (pinfunction "A2_4") (pintype "bidirectional"))
    )
    (net (code "82") (name "/PE12") (class "Default")
      (node (ref "JP1") (pin "30") (pinfunction "30_30") (pintype "passive"))
      (node (ref "U1") (pin "30") (pinfunction "P$30_30") (pintype "bidirectional"))
    )
    (net (code "83") (name "/PE13") (class "Default")
      (node (ref "JP1") (pin "29") (pinfunction "29_29") (pintype "passive"))
      (node (ref "R8") (pin "1") (pinfunction "1_1") (pintype "passive"))
      (node (ref "U1") (pin "29") (pinfunction "P$29_29") (pintype "bidirectional"))
      (node (ref "U2") (pin "5") (pinfunction "A3_5") (pintype "bidirectional"))
    )
    (net (code "84") (name "/PE14") (class "Default")
      (node (ref "JP1") (pin "32") (pinfunction "32_32") (pintype "passive"))
      (node (ref "R9") (pin "1") (pinfunction "1_1") (pintype "passive"))
      (node (ref "U1") (pin "32") (pinfunction "P$32_32") (pintype "bidirectional"))
      (node (ref "U2") (pin "6") (pinfunction "A4_6") (pintype "bidirectional"))
    )
    (net (code "85") (name "/PE15") (class "Default")
      (node (ref "JP1") (pin "31") (pinfunction "31_31") (pintype "passive"))
      (node (ref "U1") (pin "31") (pinfunction "P$31_31") (pintype "bidirectional"))
    )
    (net (code "86") (name "/PF0") (class "Default")
      (node (ref "JP2") (pin "5") (pinfunction "5_5") (pintype "passive"))
      (node (ref "U1") (pin "55") (pinfunction "P$55_55") (pintype "bidirectional"))
    )
    (net (code "87") (name "/PF1") (class "Default")
      (node (ref "JP2") (pin "6") (pinfunction "6_6") (pintype "passive"))
      (node (ref "U1") (pin "56") (pinfunction "P$56_56") (pintype "bidirectional"))
    )
    (net (code "88") (name "/PF2") (class "Default")
      (node (ref "JP1") (pin "10") (pinfunction "10_10") (pintype "passive"))
      (node (ref "U1") (pin "10") (pinfunction "P$10_10") (pintype "bidirectional"))
    )
    (net (code "89") (name "/PF4") (class "Default")
      (node (ref "JP1") (pin "13") (pinfunction "13_13") (pintype "passive"))
      (node (ref "U1") (pin "13") (pinfunction "P$13_13") (pintype "bidirectional"))
    )
    (net (code "90") (name "/PF6") (class "Default")
      (node (ref "JP2") (pin "39") (pinfunction "39_39") (pintype "passive"))
      (node (ref "U1") (pin "89") (pinfunction "P$89_89") (pintype "bidirectional"))
    )
    (net (code "91") (name "/PF9") (class "Default")
      (node (ref "JP2") (pin "3") (pinfunction "3_3") (pintype "passive"))
      (node (ref "U1") (pin "53") (pinfunction "P$53_53") (pintype "bidirectional"))
    )
    (net (code "92") (name "/PF10") (class "Default")
      (node (ref "JP2") (pin "4") (pinfunction "4_4") (pintype "passive"))
      (node (ref "U1") (pin "54") (pinfunction "P$54_54") (pintype "bidirectional"))
    )
    (net (code "93") (name "/REF") (class "Default")
      (node (ref "REF_SEL") (pin "2") (pinfunction "2_2") (pintype "passive"))
      (node (ref "U3") (pin "6") (pinfunction "REF_6") (pintype "bidirectional"))
      (node (ref "U4") (pin "6") (pinfunction "REF_6") (pintype "bidirectional"))
    )
    (net (code "94") (name "/REF_EXT") (class "Default")
      (node (ref "EXT_REF") (pin "2") (pinfunction "2_2") (pintype "passive"))
      (node (ref "REF_SEL") (pin "3") (pinfunction "3_3") (pintype "passive"))
    )
    (net (code "95") (name "/VDD") (class "Default")
      (node (ref "JP2") (pin "20") (pinfunction "20_20") (pintype "passive"))
      (node (ref "U1") (pin "70") (pinfunction "P$70_70") (pintype "bidirectional"))
    )
    (net (code "96") (name "/VDD_B") (class "Default")
      (node (ref "C3") (pin "1") (pinfunction "1_1") (pintype "passive"))
      (node (ref "LVL_EN") (pin "2") (pinfunction "2_2") (pintype "passive"))
      (node (ref "R5") (pin "1") (pinfunction "1_1") (pintype "passive"))
      (node (ref "U2") (pin "19") (pinfunction "VDD_B_19") (pintype "bidirectional"))
      (node (ref "U2") (pin "20") (pinfunction "EN_20") (pintype "bidirectional"))
    )
    (net (code "97") (name "Net-(LED1-PadA)") (class "Default")
      (node (ref "LED1") (pin "A") (pinfunction "A_A") (pintype "passive"))
      (node (ref "R26") (pin "2") (pinfunction "2_2") (pintype "passive"))
    )
    (net (code "98") (name "Net-(LED1-PadC)") (class "Default")
      (node (ref "LED1") (pin "C") (pinfunction "C_C") (pintype "passive"))
      (node (ref "PB1") (pin "B2") (pinfunction "B2_B2") (pintype "bidirectional"))
    )
    (net (code "99") (name "Net-(LED2-PadA)") (class "Default")
      (node (ref "LED2") (pin "A") (pinfunction "A_A") (pintype "passive"))
      (node (ref "R27") (pin "2") (pinfunction "2_2") (pintype "passive"))
    )
    (net (code "100") (name "Net-(LED2-PadC)") (class "Default")
      (node (ref "LED2") (pin "C") (pinfunction "C_C") (pintype "passive"))
      (node (ref "PB2") (pin "B2") (pinfunction "B2_B2") (pintype "bidirectional"))
    )
    (net (code "101") (name "Net-(LED3-PadA)") (class "Default")
      (node (ref "LED3") (pin "A") (pinfunction "A_A") (pintype "passive"))
      (node (ref "R28") (pin "2") (pinfunction "2_2") (pintype "passive"))
    )
    (net (code "102") (name "Net-(LED3-PadC)") (class "Default")
      (node (ref "LED3") (pin "C") (pinfunction "C_C") (pintype "passive"))
      (node (ref "PB3") (pin "B2") (pinfunction "B2_B2") (pintype "bidirectional"))
    )
    (net (code "103") (name "Net-(LED4-PadA)") (class "Default")
      (node (ref "LED4") (pin "A") (pinfunction "A_A") (pintype "passive"))
      (node (ref "R29") (pin "2") (pinfunction "2_2") (pintype "passive"))
    )
    (net (code "104") (name "Net-(LED4-PadC)") (class "Default")
      (node (ref "LED4") (pin "C") (pinfunction "C_C") (pintype "passive"))
      (node (ref "PB4") (pin "B2") (pinfunction "B2_B2") (pintype "bidirectional"))
    )
    (net (code "105") (name "Net-(U2-B1)") (class "Default")
      (node (ref "5V_IO") (pin "1") (pinfunction "1_1") (pintype "passive"))
      (node (ref "R14") (pin "1") (pinfunction "1_1") (pintype "passive"))
      (node (ref "U2") (pin "18") (pinfunction "B1_18") (pintype "bidirectional"))
    )
    (net (code "106") (name "Net-(U2-B2)") (class "Default")
      (node (ref "5V_IO") (pin "2") (pinfunction "2_2") (pintype "passive"))
      (node (ref "R15") (pin "1") (pinfunction "1_1") (pintype "passive"))
      (node (ref "U2") (pin "17") (pinfunction "B2_17") (pintype "bidirectional"))
    )
    (net (code "107") (name "Net-(U2-B3)") (class "Default")
      (node (ref "5V_IO") (pin "3") (pinfunction "3_3") (pintype "passive"))
      (node (ref "R16") (pin "1") (pinfunction "1_1") (pintype "passive"))
      (node (ref "U2") (pin "16") (pinfunction "B3_16") (pintype "bidirectional"))
    )
    (net (code "108") (name "Net-(U2-B4)") (class "Default")
      (node (ref "5V_IO") (pin "4") (pinfunction "4_4") (pintype "passive"))
      (node (ref "R17") (pin "1") (pinfunction "1_1") (pintype "passive"))
      (node (ref "U2") (pin "15") (pinfunction "B4_15") (pintype "bidirectional"))
    )
    (net (code "109") (name "Net-(U2-B5)") (class "Default")
      (node (ref "5V_IO") (pin "5") (pinfunction "5_5") (pintype "passive"))
      (node (ref "R18") (pin "2") (pinfunction "2_2") (pintype "passive"))
      (node (ref "U2") (pin "14") (pinfunction "B5_14") (pintype "bidirectional"))
    )
    (net (code "110") (name "Net-(U2-B6)") (class "Default")
      (node (ref "5V_IO") (pin "6") (pinfunction "6_6") (pintype "passive"))
      (node (ref "R19") (pin "2") (pinfunction "2_2") (pintype "passive"))
      (node (ref "U2") (pin "13") (pinfunction "B6_13") (pintype "bidirectional"))
    )
    (net (code "111") (name "Net-(U2-B7)") (class "Default")
      (node (ref "5V_IO") (pin "7") (pinfunction "7_7") (pintype "passive"))
      (node (ref "R20") (pin "2") (pinfunction "2_2") (pintype "passive"))
      (node (ref "U2") (pin "12") (pinfunction "B7_12") (pintype "bidirectional"))
    )
    (net (code "112") (name "Net-(U2-B8)") (class "Default")
      (node (ref "5V_IO") (pin "8") (pinfunction "8_8") (pintype "passive"))
      (node (ref "R21") (pin "2") (pinfunction "2_2") (pintype "passive"))
      (node (ref "U2") (pin "11") (pinfunction "B8_11") (pintype "bidirectional"))
    )
    (net (code "113") (name "Net-(U3-IN+)") (class "Default")
      (node (ref "AIN1") (pin "2") (pinfunction "2_2") (pintype "passive"))
      (node (ref "U3") (pin "4") (pinfunction "IN+_4") (pintype "bidirectional"))
    )
    (net (code "114") (name "Net-(U3-IN-)") (class "Default")
      (node (ref "AIN1") (pin "1") (pinfunction "1_1") (pintype "passive"))
      (node (ref "U3") (pin "1") (pinfunction "IN-_1") (pintype "bidirectional"))
    )
    (net (code "115") (name "Net-(U3-RG+)") (class "Default")
      (node (ref "R1") (pin "2") (pinfunction "2_2") (pintype "passive"))
      (node (ref "U3") (pin "2") (pinfunction "RG+_2") (pintype "bidirectional"))
    )
    (net (code "116") (name "Net-(U3-RG-)") (class "Default")
      (node (ref "R1") (pin "1") (pinfunction "1_1") (pintype "passive"))
      (node (ref "U3") (pin "3") (pinfunction "RG-_3") (pintype "bidirectional"))
    )
    (net (code "117") (name "Net-(U3-VOUT)") (class "Default")
      (node (ref "R4") (pin "2") (pinfunction "2_2") (pintype "passive"))
      (node (ref "U3") (pin "7") (pinfunction "VOUT_7") (pintype "bidirectional"))
    )
    (net (code "118") (name "Net-(U4-IN+)") (class "Default")
      (node (ref "AIN2") (pin "2") (pinfunction "2_2") (pintype "passive"))
      (node (ref "U4") (pin "4") (pinfunction "IN+_4") (pintype "bidirectional"))
    )
    (net (code "119") (name "Net-(U4-IN-)") (class "Default")
      (node (ref "AIN2") (pin "1") (pinfunction "1_1") (pintype "passive"))
      (node (ref "U4") (pin "1") (pinfunction "IN-_1") (pintype "bidirectional"))
    )
    (net (code "120") (name "Net-(U4-RG+)") (class "Default")
      (node (ref "R2") (pin "2") (pinfunction "2_2") (pintype "passive"))
      (node (ref "U4") (pin "2") (pinfunction "RG+_2") (pintype "bidirectional"))
    )
    (net (code "121") (name "Net-(U4-RG-)") (class "Default")
      (node (ref "R2") (pin "1") (pinfunction "1_1") (pintype "passive"))
      (node (ref "U4") (pin "3") (pinfunction "RG-_3") (pintype "bidirectional"))
    )
    (net (code "122") (name "Net-(U4-VOUT)") (class "Default")
      (node (ref "R3") (pin "2") (pinfunction "2_2") (pintype "passive"))
      (node (ref "U4") (pin "7") (pinfunction "VOUT_7") (pintype "bidirectional"))
    )
    (net (code "123") (name "unconnected-(JP2-Pad48)") (class "Default")
      (node (ref "JP2") (pin "48") (pinfunction "48_48") (pintype "passive"))
    )
    (net (code "124") (name "unconnected-(PB1-PadA1)") (class "Default")
      (node (ref "PB1") (pin "A1") (pinfunction "A1_A1") (pintype "bidirectional"))
    )
    (net (code "125") (name "unconnected-(PB1-PadA2)") (class "Default")
      (node (ref "PB1") (pin "A2") (pinfunction "A2_A2") (pintype "bidirectional"))
    )
    (net (code "126") (name "unconnected-(PB2-PadA1)") (class "Default")
      (node (ref "PB2") (pin "A1") (pinfunction "A1_A1") (pintype "bidirectional"))
    )
    (net (code "127") (name "unconnected-(PB2-PadA2)") (class "Default")
      (node (ref "PB2") (pin "A2") (pinfunction "A2_A2") (pintype "bidirectional"))
    )
    (net (code "128") (name "unconnected-(PB3-PadA1)") (class "Default")
      (node (ref "PB3") (pin "A1") (pinfunction "A1_A1") (pintype "bidirectional"))
    )
    (net (code "129") (name "unconnected-(PB3-PadA2)") (class "Default")
      (node (ref "PB3") (pin "A2") (pinfunction "A2_A2") (pintype "bidirectional"))
    )
    (net (code "130") (name "unconnected-(PB4-PadA1)") (class "Default")
      (node (ref "PB4") (pin "A1") (pinfunction "A1_A1") (pintype "bidirectional"))
    )
    (net (code "131") (name "unconnected-(PB4-PadA2)") (class "Default")
      (node (ref "PB4") (pin "A2") (pinfunction "A2_A2") (pintype "bidirectional"))
    )
    (net (code "132") (name "unconnected-(U1-P$98-Pad98)") (class "Default")
      (node (ref "U1") (pin "98") (pinfunction "P$98_98") (pintype "bidirectional"))
    )
  )
)
